# CAN-to-CAN.net
KiCad netlist of a schematic drawn in Altium Designer
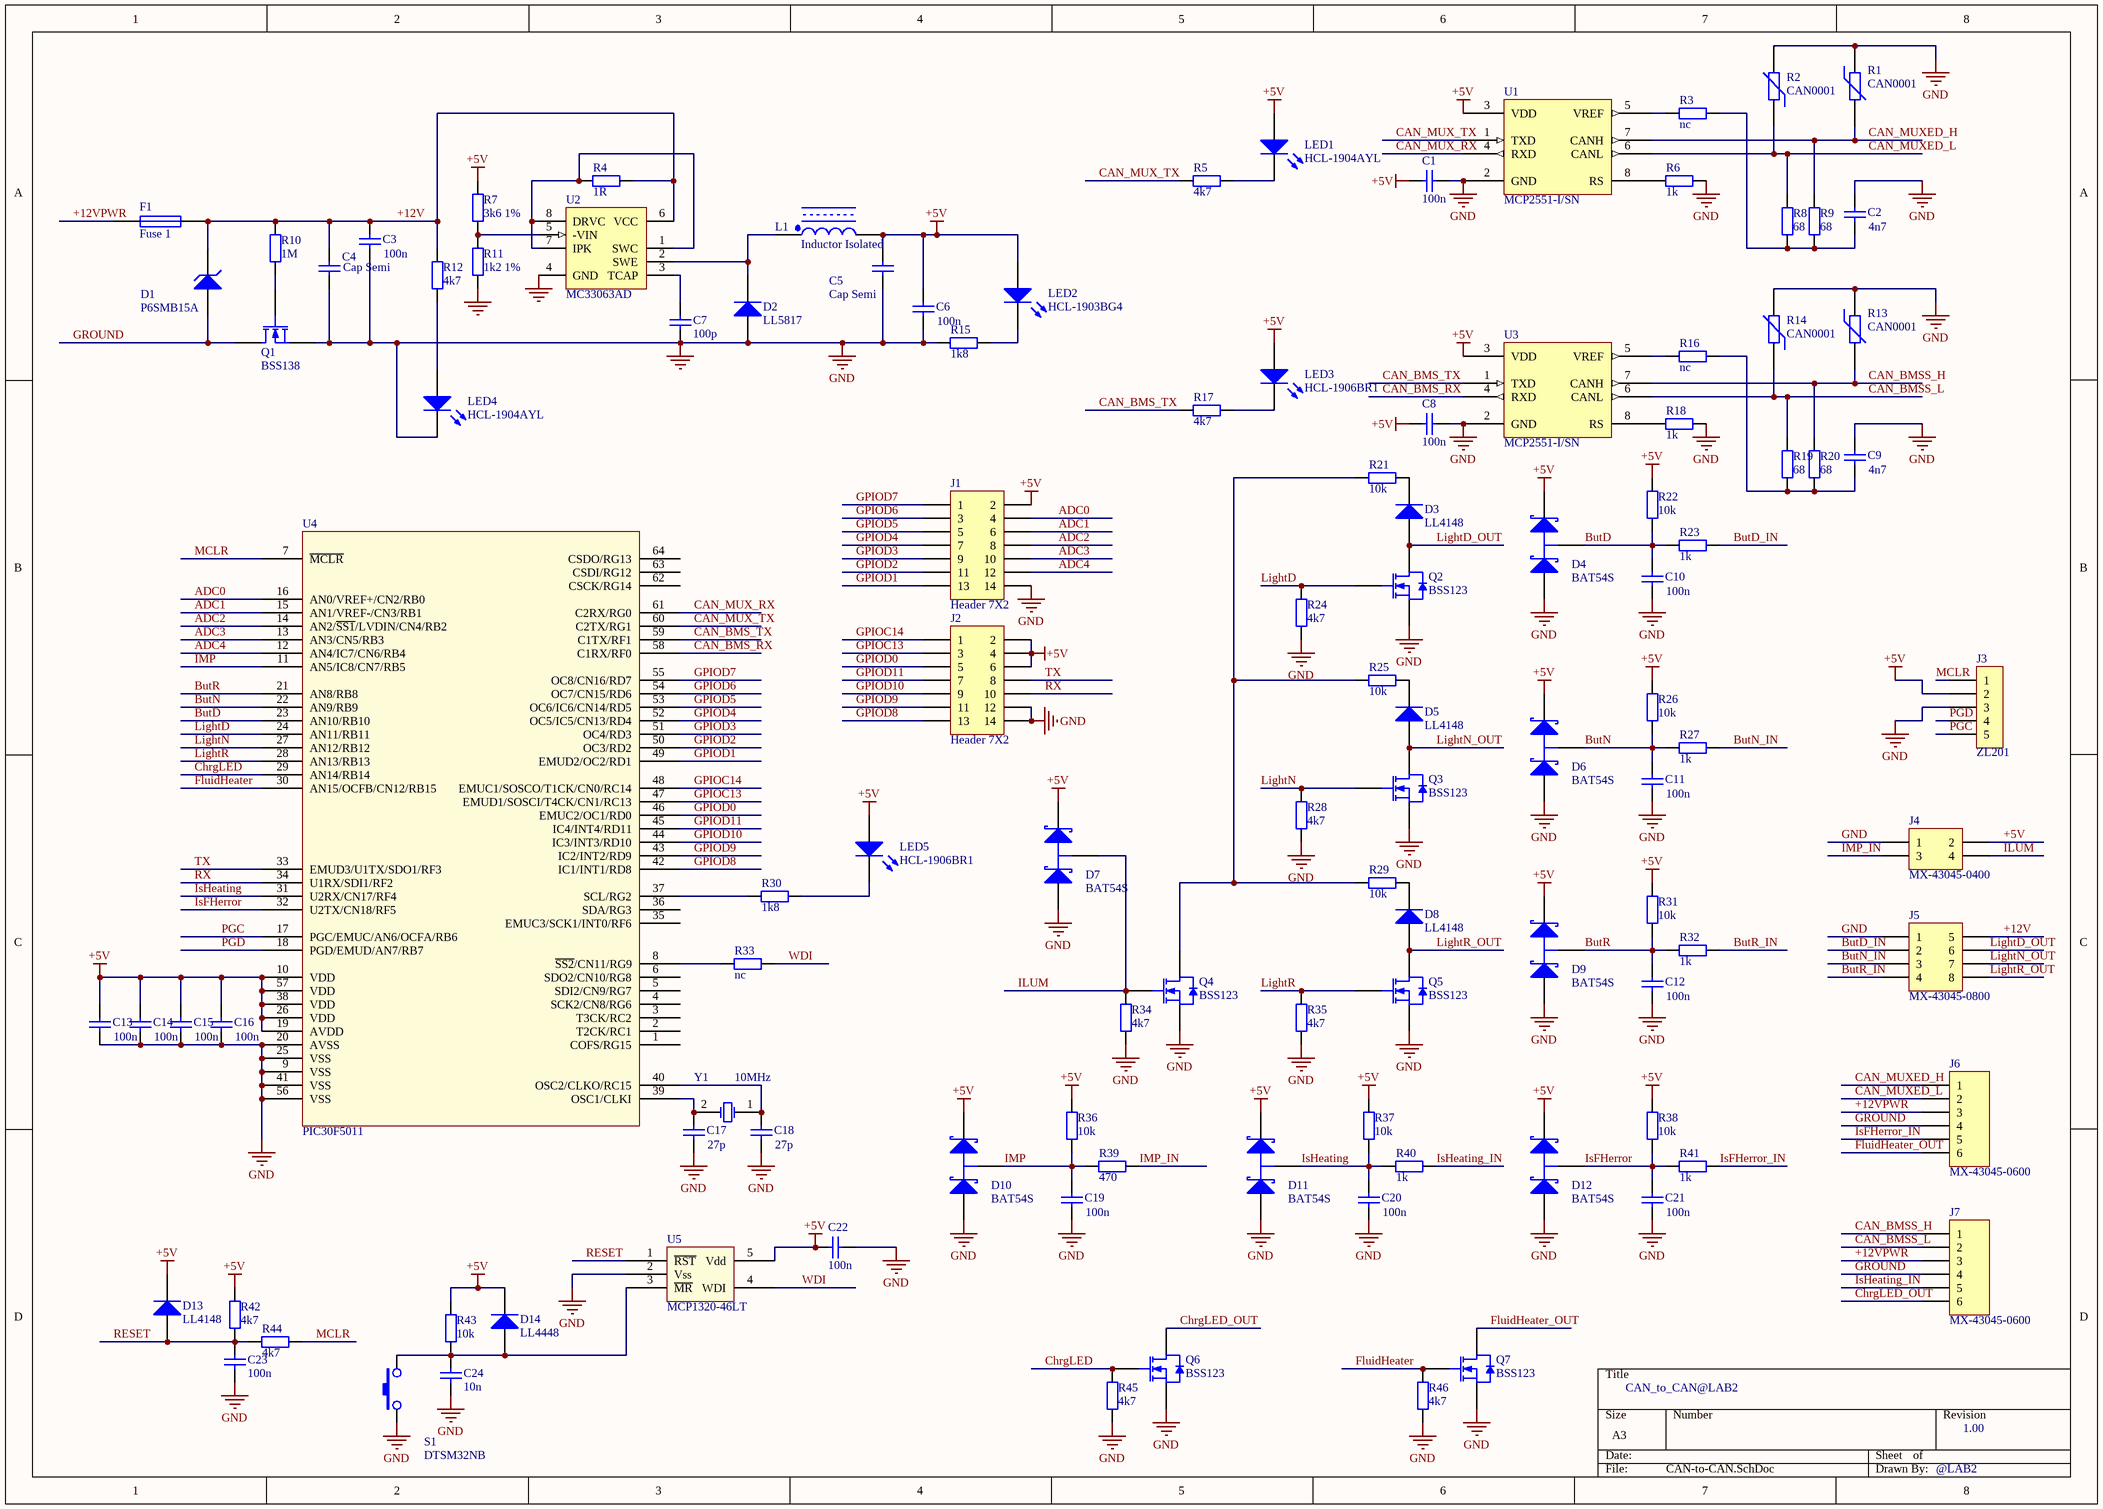
[diagram p0: CAN-to-CAN.SchDoc]

(export (version "E")
  (design (tool "Eeschema 10.0.6"))
  (components
    (comp (ref "C1")
      (value "100n")
      (footprint "0603")
      (description "Capacitor")
      (libsource (lib "Miscellaneous Devices") (part "Cap"))
    )
    (comp (ref "C2")
      (value "4n7")
      (footprint "0603")
      (description "Capacitor")
      (libsource (lib "Miscellaneous Devices") (part "Cap"))
    )
    (comp (ref "C3")
      (value "100n")
      (footprint "6-0805_N")
      (description "Capacitor")
      (libsource (lib "Miscellaneous Devices") (part "Cap"))
    )
    (comp (ref "C4")
      (value "Cap Semi")
      (footprint "C1206")
      (description "Capacitor (Semiconductor SIM Model)")
      (libsource (lib "Miscellaneous Devices") (part "Cap Semi"))
    )
    (comp (ref "C5")
      (value "Cap Semi")
      (footprint "C1206")
      (description "Capacitor (Semiconductor SIM Model)")
      (libsource (lib "Miscellaneous Devices") (part "Cap Semi"))
    )
    (comp (ref "C6")
      (value "100n")
      (footprint "0603")
      (description "Capacitor")
      (libsource (lib "Miscellaneous Devices") (part "Cap"))
    )
    (comp (ref "C7")
      (value "100p")
      (footprint "0603")
      (description "Capacitor")
      (libsource (lib "Miscellaneous Devices") (part "Cap"))
    )
    (comp (ref "C8")
      (value "100n")
      (footprint "0603")
      (description "Capacitor")
      (libsource (lib "Miscellaneous Devices") (part "Cap"))
    )
    (comp (ref "C9")
      (value "4n7")
      (footprint "0603")
      (description "Capacitor")
      (libsource (lib "Miscellaneous Devices") (part "Cap"))
    )
    (comp (ref "C10")
      (value "100n")
      (footprint "0603")
      (description "Capacitor")
      (libsource (lib "Miscellaneous Devices") (part "Cap"))
    )
    (comp (ref "C11")
      (value "100n")
      (footprint "0603")
      (description "Capacitor")
      (libsource (lib "Miscellaneous Devices") (part "Cap"))
    )
    (comp (ref "C12")
      (value "100n")
      (footprint "0603")
      (description "Capacitor")
      (libsource (lib "Miscellaneous Devices") (part "Cap"))
    )
    (comp (ref "C13")
      (value "100n")
      (footprint "0603")
      (description "Capacitor")
      (libsource (lib "Miscellaneous Devices") (part "Cap"))
    )
    (comp (ref "C14")
      (value "100n")
      (footprint "0603")
      (description "Capacitor")
      (libsource (lib "Miscellaneous Devices") (part "Cap"))
    )
    (comp (ref "C15")
      (value "100n")
      (footprint "0603")
      (description "Capacitor")
      (libsource (lib "Miscellaneous Devices") (part "Cap"))
    )
    (comp (ref "C16")
      (value "100n")
      (footprint "0603")
      (description "Capacitor")
      (libsource (lib "Miscellaneous Devices") (part "Cap"))
    )
    (comp (ref "C17")
      (value "27p")
      (footprint "0603")
      (description "Capacitor")
      (libsource (lib "Miscellaneous Devices") (part "Cap"))
    )
    (comp (ref "C18")
      (value "27p")
      (footprint "0603")
      (description "Capacitor")
      (libsource (lib "Miscellaneous Devices") (part "Cap"))
    )
    (comp (ref "C19")
      (value "100n")
      (footprint "0603")
      (description "Capacitor")
      (libsource (lib "Miscellaneous Devices") (part "Cap"))
    )
    (comp (ref "C20")
      (value "100n")
      (footprint "0603")
      (description "Capacitor")
      (libsource (lib "Miscellaneous Devices") (part "Cap"))
    )
    (comp (ref "C21")
      (value "100n")
      (footprint "0603")
      (description "Capacitor")
      (libsource (lib "Miscellaneous Devices") (part "Cap"))
    )
    (comp (ref "C22")
      (value "100n")
      (footprint "0603")
      (description "Capacitor")
      (libsource (lib "Miscellaneous Devices") (part "Cap"))
    )
    (comp (ref "C23")
      (value "100n")
      (footprint "0603")
      (description "Capacitor")
      (libsource (lib "Miscellaneous Devices") (part "Cap"))
    )
    (comp (ref "C24")
      (value "10n")
      (footprint "0603")
      (description "Capacitor")
      (libsource (lib "Miscellaneous Devices") (part "Cap"))
    )
    (comp (ref "D1")
      (value "P6SMB15A")
      (footprint "SMB")
      (description "Zener Diode")
      (libsource (lib "Miscellaneous Devices") (part "D Zener"))
    )
    (comp (ref "D2")
      (value "LL5817")
      (footprint "DIODE_SMC")
      (description "High Conductance Fast Diode")
      (libsource (lib "FSC Discrete Diode") (part "1N4148"))
    )
    (comp (ref "D3")
      (value "LL4148")
      (footprint "DIODE_SMC")
      (description "High Conductance Fast Diode")
      (libsource (lib "FSC Discrete Diode") (part "1N4148"))
    )
    (comp (ref "D4")
      (value "BAT54S")
      (footprint "SOT23_M")
      (description "Schottky Barrier Double Diode")
      (libsource (lib "Philips Discrete Diode - Schottky") (part "BAT54S"))
    )
    (comp (ref "D5")
      (value "LL4148")
      (footprint "DIODE_SMC")
      (description "High Conductance Fast Diode")
      (libsource (lib "FSC Discrete Diode") (part "1N4148"))
    )
    (comp (ref "D6")
      (value "BAT54S")
      (footprint "SOT23_M")
      (description "Schottky Barrier Double Diode")
      (libsource (lib "Philips Discrete Diode - Schottky") (part "BAT54S"))
    )
    (comp (ref "D7")
      (value "BAT54S")
      (footprint "SOT23_M")
      (description "Schottky Barrier Double Diode")
      (libsource (lib "Philips Discrete Diode - Schottky") (part "BAT54S"))
    )
    (comp (ref "D8")
      (value "LL4148")
      (footprint "DIODE_SMC")
      (description "High Conductance Fast Diode")
      (libsource (lib "FSC Discrete Diode") (part "1N4148"))
    )
    (comp (ref "D9")
      (value "BAT54S")
      (footprint "SOT23_M")
      (description "Schottky Barrier Double Diode")
      (libsource (lib "Philips Discrete Diode - Schottky") (part "BAT54S"))
    )
    (comp (ref "D10")
      (value "BAT54S")
      (footprint "SOT23_M")
      (description "Schottky Barrier Double Diode")
      (libsource (lib "Philips Discrete Diode - Schottky") (part "BAT54S"))
    )
    (comp (ref "D11")
      (value "BAT54S")
      (footprint "SOT23_M")
      (description "Schottky Barrier Double Diode")
      (libsource (lib "Philips Discrete Diode - Schottky") (part "BAT54S"))
    )
    (comp (ref "D12")
      (value "BAT54S")
      (footprint "SOT23_M")
      (description "Schottky Barrier Double Diode")
      (libsource (lib "Philips Discrete Diode - Schottky") (part "BAT54S"))
    )
    (comp (ref "D13")
      (value "LL4148")
      (footprint "DIODE_SMC")
      (description "High Conductance Fast Diode")
      (libsource (lib "FSC Discrete Diode") (part "1N4148"))
    )
    (comp (ref "D14")
      (value "LL4448")
      (footprint "DIODE_SMC")
      (description "Default Diode")
      (libsource (lib "Miscellaneous Devices") (part "Diode"))
    )
    (comp (ref "F1")
      (value "Fuse 1")
      (footprint "1812")
      (description "Fuse")
      (libsource (lib "Miscellaneous Devices") (part "Fuse 1"))
    )
    (comp (ref "J1")
      (value "Header 7X2")
      (footprint "HDR2X7")
      (description "Header, 7-Pin, Dual row")
      (libsource (lib "Miscellaneous Connectors") (part "Header 7X2"))
    )
    (comp (ref "J2")
      (value "Header 7X2")
      (footprint "HDR2X7")
      (description "Header, 7-Pin, Dual row")
      (libsource (lib "Miscellaneous Connectors") (part "Header 7X2"))
    )
    (comp (ref "J3")
      (value "ZL201")
      (footprint "HDR1X5")
      (description "Connector")
      (libsource (lib "*") (part "CON5"))
    )
    (comp (ref "J4")
      (value "MX-43045-0400")
      (footprint "HDR2X2")
      (description "Header, 2-Pin, Dual row")
      (libsource (lib "Miscellaneous Connectors") (part "Header 2X2"))
    )
    (comp (ref "J5")
      (value "MX-43045-0800")
      (footprint "HDR2X4")
      (description "Header, 4-Pin, Dual row")
      (libsource (lib "Miscellaneous Connectors") (part "Header 4X2A"))
    )
    (comp (ref "J6")
      (value "MX-43045-0600")
      (footprint "Miscellaneous Connectors:HDR2X3")
      (description "Header, 6-Pin")
      (libsource (lib "Miscellaneous Connectors") (part "Header 6"))
    )
    (comp (ref "J7")
      (value "MX-43045-0600")
      (footprint "HDR2X3")
      (description "Header, 6-Pin")
      (libsource (lib "Miscellaneous Connectors") (part "Header 6"))
    )
    (comp (ref "L1")
      (value "Inductor Isolated")
      (footprint "425")
      (description "Isolated Inductor")
      (libsource (lib "Miscellaneous Devices") (part "Inductor Isolated"))
    )
    (comp (ref "LED1")
      (value "HCL-1904AYL")
      (footprint "0603")
      (description "Typical BLUE SiC LED")
      (libsource (lib "Miscellaneous Devices") (part "LED3"))
    )
    (comp (ref "LED2")
      (value "HCL-1903BG4")
      (footprint "0603")
      (description "Typical BLUE SiC LED")
      (libsource (lib "Miscellaneous Devices") (part "LED3"))
    )
    (comp (ref "LED3")
      (value "HCL-1906BR1")
      (footprint "0603")
      (description "Typical BLUE SiC LED")
      (libsource (lib "Miscellaneous Devices") (part "LED3"))
    )
    (comp (ref "LED4")
      (value "HCL-1904AYL")
      (footprint "0603")
      (description "Typical BLUE SiC LED")
      (libsource (lib "Miscellaneous Devices") (part "LED3"))
    )
    (comp (ref "LED5")
      (value "HCL-1906BR1")
      (footprint "0603")
      (description "Typical BLUE SiC LED")
      (libsource (lib "Miscellaneous Devices") (part "LED3"))
    )
    (comp (ref "Q1")
      (value "BSS138")
      (footprint "SOT-23_M")
      (description "N-Channel Enhancement Mode Vertical DMOS FET")
      (libsource (lib "Zetex Discrete MOSFET") (part "BSS138"))
    )
    (comp (ref "Q2")
      (value "BSS123")
      (footprint "SOT23_M")
      (description "N-channel Enhancement Mode Vertical D-MOSFET")
      (libsource (lib "Philips Discrete MOSFET - Low Power") (part "BSS123"))
    )
    (comp (ref "Q3")
      (value "BSS123")
      (footprint "SOT23_M")
      (description "N-channel Enhancement Mode Vertical D-MOSFET")
      (libsource (lib "Philips Discrete MOSFET - Low Power") (part "BSS123"))
    )
    (comp (ref "Q4")
      (value "BSS123")
      (footprint "SOT23_M")
      (description "N-channel Enhancement Mode Vertical D-MOSFET")
      (libsource (lib "Philips Discrete MOSFET - Low Power") (part "BSS123"))
    )
    (comp (ref "Q5")
      (value "BSS123")
      (footprint "SOT23_M")
      (description "N-channel Enhancement Mode Vertical D-MOSFET")
      (libsource (lib "Philips Discrete MOSFET - Low Power") (part "BSS123"))
    )
    (comp (ref "Q6")
      (value "BSS123")
      (footprint "SOT23_N")
      (description "N-channel Enhancement Mode Vertical D-MOSFET")
      (libsource (lib "Philips Discrete MOSFET - Low Power") (part "BSS123"))
    )
    (comp (ref "Q7")
      (value "BSS123")
      (footprint "SOT23_M")
      (description "N-channel Enhancement Mode Vertical D-MOSFET")
      (libsource (lib "Philips Discrete MOSFET - Low Power") (part "BSS123"))
    )
    (comp (ref "R1")
      (value "CAN0001")
      (footprint "0603")
      (description "Varistor (Voltage-Sensitive Resistor)")
      (libsource (lib "Miscellaneous Devices") (part "Res Varistor"))
    )
    (comp (ref "R2")
      (value "CAN0001")
      (footprint "0603")
      (description "Varistor (Voltage-Sensitive Resistor)")
      (libsource (lib "Miscellaneous Devices") (part "Res Varistor"))
    )
    (comp (ref "R3")
      (value "nc")
      (footprint "0603")
      (description "Resistor")
      (libsource (lib "") (part "Res2_2"))
    )
    (comp (ref "R4")
      (value "1R")
      (footprint "AXIAL-0.4")
      (description "Resistor")
      (libsource (lib "") (part "Res2_2"))
    )
    (comp (ref "R5")
      (value "4k7")
      (footprint "0603")
      (description "Resistor")
      (libsource (lib "Miscellaneous Devices") (part "Res2"))
    )
    (comp (ref "R6")
      (value "1k")
      (footprint "0603")
      (description "Resistor")
      (libsource (lib "") (part "Res2_2"))
    )
    (comp (ref "R7")
      (value "3k6 1%")
      (footprint "0603")
      (description "Resistor")
      (libsource (lib "") (part "Res2_1"))
    )
    (comp (ref "R8")
      (value "68")
      (footprint "0603")
      (description "Resistor")
      (libsource (lib "") (part "Res2_1"))
    )
    (comp (ref "R9")
      (value "68")
      (footprint "0603")
      (description "Resistor")
      (libsource (lib "") (part "Res2_1"))
    )
    (comp (ref "R10")
      (value "1M")
      (footprint "0603")
      (description "Resistor")
      (libsource (lib "") (part "Res2_1"))
    )
    (comp (ref "R11")
      (value "1k2 1%")
      (footprint "0603")
      (description "Resistor")
      (libsource (lib "") (part "Res2_3"))
    )
    (comp (ref "R12")
      (value "4k7")
      (footprint "0603")
      (description "Resistor")
      (libsource (lib "") (part "Res2_1"))
    )
    (comp (ref "R13")
      (value "CAN0001")
      (footprint "0603")
      (description "Varistor (Voltage-Sensitive Resistor)")
      (libsource (lib "Miscellaneous Devices") (part "Res Varistor"))
    )
    (comp (ref "R14")
      (value "CAN0001")
      (footprint "0603")
      (description "Varistor (Voltage-Sensitive Resistor)")
      (libsource (lib "Miscellaneous Devices") (part "Res Varistor"))
    )
    (comp (ref "R15")
      (value "1k8")
      (footprint "0603")
      (description "Resistor")
      (libsource (lib "Miscellaneous Devices") (part "Res2"))
    )
    (comp (ref "R16")
      (value "nc")
      (footprint "0603")
      (description "Resistor")
      (libsource (lib "") (part "Res2_2"))
    )
    (comp (ref "R17")
      (value "4k7")
      (footprint "0603")
      (description "Resistor")
      (libsource (lib "Miscellaneous Devices") (part "Res2"))
    )
    (comp (ref "R18")
      (value "1k")
      (footprint "0603")
      (description "Resistor")
      (libsource (lib "") (part "Res2_2"))
    )
    (comp (ref "R19")
      (value "68")
      (footprint "0603")
      (description "Resistor")
      (libsource (lib "") (part "Res2_1"))
    )
    (comp (ref "R20")
      (value "68")
      (footprint "0603")
      (description "Resistor")
      (libsource (lib "") (part "Res2_1"))
    )
    (comp (ref "R21")
      (value "10k")
      (footprint "0603")
      (description "Resistor")
      (libsource (lib "") (part "Res2_2"))
    )
    (comp (ref "R22")
      (value "10k")
      (footprint "0603")
      (description "Resistor")
      (libsource (lib "") (part "Res2_1"))
    )
    (comp (ref "R23")
      (value "1k")
      (footprint "0603")
      (description "Resistor")
      (libsource (lib "Miscellaneous Devices") (part "Res2"))
    )
    (comp (ref "R24")
      (value "4k7")
      (footprint "0603")
      (description "Resistor")
      (libsource (lib "") (part "Res2_1"))
    )
    (comp (ref "R25")
      (value "10k")
      (footprint "0603")
      (description "Resistor")
      (libsource (lib "") (part "Res2_2"))
    )
    (comp (ref "R26")
      (value "10k")
      (footprint "0603")
      (description "Resistor")
      (libsource (lib "") (part "Res2_1"))
    )
    (comp (ref "R27")
      (value "1k")
      (footprint "0603")
      (description "Resistor")
      (libsource (lib "Miscellaneous Devices") (part "Res2"))
    )
    (comp (ref "R28")
      (value "4k7")
      (footprint "0603")
      (description "Resistor")
      (libsource (lib "") (part "Res2_1"))
    )
    (comp (ref "R29")
      (value "10k")
      (footprint "0603")
      (description "Resistor")
      (libsource (lib "") (part "Res2_2"))
    )
    (comp (ref "R30")
      (value "1k8")
      (footprint "0603")
      (description "Resistor")
      (libsource (lib "Miscellaneous Devices") (part "Res2"))
    )
    (comp (ref "R31")
      (value "10k")
      (footprint "0603")
      (description "Resistor")
      (libsource (lib "") (part "Res2_1"))
    )
    (comp (ref "R32")
      (value "1k")
      (footprint "0603")
      (description "Resistor")
      (libsource (lib "Miscellaneous Devices") (part "Res2"))
    )
    (comp (ref "R33")
      (value "nc")
      (footprint "0603")
      (description "Resistor")
      (libsource (lib "Miscellaneous Devices") (part "Res2"))
    )
    (comp (ref "R34")
      (value "4k7")
      (footprint "0603")
      (description "Resistor")
      (libsource (lib "") (part "Res2_1"))
    )
    (comp (ref "R35")
      (value "4k7")
      (footprint "0603")
      (description "Resistor")
      (libsource (lib "") (part "Res2_1"))
    )
    (comp (ref "R36")
      (value "10k")
      (footprint "0603")
      (description "Resistor")
      (libsource (lib "") (part "Res2_1"))
    )
    (comp (ref "R37")
      (value "10k")
      (footprint "0603")
      (description "Resistor")
      (libsource (lib "") (part "Res2_1"))
    )
    (comp (ref "R38")
      (value "10k")
      (footprint "0603")
      (description "Resistor")
      (libsource (lib "") (part "Res2_1"))
    )
    (comp (ref "R39")
      (value "470")
      (footprint "0603")
      (description "Resistor")
      (libsource (lib "Miscellaneous Devices") (part "Res2"))
    )
    (comp (ref "R40")
      (value "1k")
      (footprint "0603")
      (description "Resistor")
      (libsource (lib "Miscellaneous Devices") (part "Res2"))
    )
    (comp (ref "R41")
      (value "1k")
      (footprint "0603")
      (description "Resistor")
      (libsource (lib "Miscellaneous Devices") (part "Res2"))
    )
    (comp (ref "R42")
      (value "4k7")
      (footprint "0603")
      (description "Resistor")
      (libsource (lib "") (part "Res2_1"))
    )
    (comp (ref "R43")
      (value "10k")
      (footprint "0603")
      (description "Resistor")
      (libsource (lib "") (part "Res2_3"))
    )
    (comp (ref "R44")
      (value "4k7")
      (footprint "0603")
      (description "Resistor")
      (libsource (lib "Miscellaneous Devices") (part "Res2"))
    )
    (comp (ref "R45")
      (value "4k7")
      (footprint "0603")
      (description "Resistor")
      (libsource (lib "") (part "Res2_1"))
    )
    (comp (ref "R46")
      (value "4k7")
      (footprint "0603")
      (description "Resistor")
      (libsource (lib "") (part "Res2_1"))
    )
    (comp (ref "S1")
      (value "DTSM32NB")
      (footprint "0603")
      (description "Switch PushButton")
      (libsource (lib "*") (part "PUSHB"))
    )
    (comp (ref "U1")
      (value "MCP2551-I/SN")
      (footprint "SO8_L")
      (description "High Speed CAN Transceiver, 8-Pin Plastic SOIC, Industrial Grade")
      (libsource (lib "Microchip Interface Line Transceiver") (part "MCP2551-I/SN"))
    )
    (comp (ref "U2")
      (value "MC33063AD")
      (footprint "SO8_N")
      (description "DC-to-DC Converter Control Circuit")
      (libsource (lib "Motorola Power Mgt DC-DC Converter") (part "MC33063AD"))
    )
    (comp (ref "U3")
      (value "MCP2551-I/SN")
      (footprint "SO8_L")
      (description "High Speed CAN Transceiver, 8-Pin Plastic SOIC, Industrial Grade")
      (libsource (lib "Microchip Interface Line Transceiver") (part "MCP2551-I/SN"))
    )
    (comp (ref "U4")
      (value "PIC30F5011")
      (footprint "ST-64-2_M")
      (description "PIC30F5011 - Up")
      (libsource (lib "X-Tro's Misc") (part "PIC30F5011"))
    )
    (comp (ref "U5")
      (value "MCP1320-46LT")
      (footprint "SOT23-6_L")
      (libsource (lib "X-Tro's Misc") (part "MCP1320"))
    )
    (comp (ref "Y1")
      (value "10MHz")
      (footprint "3.2X1.6X1.1")
      (description "Crystal Oscillator")
      (libsource (lib "Miscellaneous Devices") (part "XTAL"))
    )
  )
  (nets
    (net (code "1") (name "+5V") (class "Default")
      (node (ref "C1") (pin "1") (pinfunction "1_1") (pintype "passive"))
      (node (ref "C13") (pin "1") (pinfunction "1_1") (pintype "passive"))
      (node (ref "C14") (pin "1") (pinfunction "1_1") (pintype "passive"))
      (node (ref "C15") (pin "1") (pinfunction "1_1") (pintype "passive"))
      (node (ref "C16") (pin "1") (pinfunction "1_1") (pintype "passive"))
      (node (ref "C22") (pin "1") (pinfunction "1_1") (pintype "passive"))
      (node (ref "C5") (pin "1") (pinfunction "1_1") (pintype "passive"))
      (node (ref "C6") (pin "1") (pinfunction "1_1") (pintype "passive"))
      (node (ref "C8") (pin "1") (pinfunction "1_1") (pintype "passive"))
      (node (ref "D10") (pin "2") (pinfunction "K_2") (pintype "passive"))
      (node (ref "D11") (pin "2") (pinfunction "K_2") (pintype "passive"))
      (node (ref "D12") (pin "2") (pinfunction "K_2") (pintype "passive"))
      (node (ref "D13") (pin "2") (pinfunction "K_2") (pintype "passive"))
      (node (ref "D14") (pin "2") (pinfunction "K_2") (pintype "passive"))
      (node (ref "D4") (pin "2") (pinfunction "K_2") (pintype "passive"))
      (node (ref "D6") (pin "2") (pinfunction "K_2") (pintype "passive"))
      (node (ref "D7") (pin "2") (pinfunction "K_2") (pintype "passive"))
      (node (ref "D9") (pin "2") (pinfunction "K_2") (pintype "passive"))
      (node (ref "J1") (pin "2") (pinfunction "2_2") (pintype "passive"))
      (node (ref "J2") (pin "2") (pinfunction "2_2") (pintype "passive"))
      (node (ref "J2") (pin "4") (pinfunction "4_4") (pintype "passive"))
      (node (ref "J2") (pin "6") (pinfunction "6_6") (pintype "passive"))
      (node (ref "J3") (pin "2") (pinfunction "2_2") (pintype "passive"))
      (node (ref "J4") (pin "2") (pinfunction "2_2") (pintype "passive"))
      (node (ref "L1") (pin "2") (pinfunction "2_2") (pintype "passive"))
      (node (ref "LED1") (pin "1") (pinfunction "A_1") (pintype "passive"))
      (node (ref "LED2") (pin "1") (pinfunction "A_1") (pintype "passive"))
      (node (ref "LED3") (pin "1") (pinfunction "A_1") (pintype "passive"))
      (node (ref "LED5") (pin "1") (pinfunction "A_1") (pintype "passive"))
      (node (ref "R22") (pin "1") (pinfunction "1_1") (pintype "passive"))
      (node (ref "R26") (pin "1") (pinfunction "1_1") (pintype "passive"))
      (node (ref "R31") (pin "1") (pinfunction "1_1") (pintype "passive"))
      (node (ref "R36") (pin "1") (pinfunction "1_1") (pintype "passive"))
      (node (ref "R37") (pin "1") (pinfunction "1_1") (pintype "passive"))
      (node (ref "R38") (pin "1") (pinfunction "1_1") (pintype "passive"))
      (node (ref "R42") (pin "1") (pinfunction "1_1") (pintype "passive"))
      (node (ref "R43") (pin "2") (pinfunction "2_2") (pintype "passive"))
      (node (ref "R7") (pin "1") (pinfunction "1_1") (pintype "passive"))
      (node (ref "U1") (pin "3") (pinfunction "VDD_3") (pintype "power_in"))
      (node (ref "U3") (pin "3") (pinfunction "VDD_3") (pintype "power_in"))
      (node (ref "U4") (pin "10") (pinfunction "VDD_10") (pintype "passive"))
      (node (ref "U4") (pin "19") (pinfunction "AVDD_19") (pintype "passive"))
      (node (ref "U4") (pin "26") (pinfunction "VDD_26") (pintype "passive"))
      (node (ref "U4") (pin "38") (pinfunction "VDD_38") (pintype "passive"))
      (node (ref "U4") (pin "57") (pinfunction "VDD_57") (pintype "passive"))
      (node (ref "U5") (pin "5") (pinfunction "Vdd_5") (pintype "passive"))
    )
    (net (code "2") (name "/+12V") (class "Default")
      (node (ref "C3") (pin "1") (pinfunction "1_1") (pintype "passive"))
      (node (ref "C4") (pin "1") (pinfunction "1_1") (pintype "passive"))
      (node (ref "D1") (pin "2") (pinfunction "K_2") (pintype "passive"))
      (node (ref "F1") (pin "2") (pinfunction "2_2") (pintype "passive"))
      (node (ref "J5") (pin "5") (pinfunction "5_5") (pintype "passive"))
      (node (ref "R10") (pin "1") (pinfunction "1_1") (pintype "passive"))
      (node (ref "R12") (pin "1") (pinfunction "1_1") (pintype "passive"))
      (node (ref "R4") (pin "2") (pinfunction "2_2") (pintype "passive"))
      (node (ref "U2") (pin "6") (pinfunction "VCC_6") (pintype "power_in"))
    )
    (net (code "3") (name "/+12VPWR") (class "Default")
      (node (ref "F1") (pin "1") (pinfunction "1_1") (pintype "passive"))
      (node (ref "J6") (pin "3") (pinfunction "3_3") (pintype "passive"))
      (node (ref "J7") (pin "3") (pinfunction "3_3") (pintype "passive"))
    )
    (net (code "4") (name "/ADC0") (class "Default")
      (node (ref "J1") (pin "4") (pinfunction "4_4") (pintype "passive"))
      (node (ref "U4") (pin "16") (pinfunction "AN0/VREF+/CN2/RB0_16") (pintype "passive"))
    )
    (net (code "5") (name "/ADC1") (class "Default")
      (node (ref "J1") (pin "6") (pinfunction "6_6") (pintype "passive"))
      (node (ref "U4") (pin "15") (pinfunction "AN1/VREF-/CN3/RB1_15") (pintype "passive"))
    )
    (net (code "6") (name "/ADC2") (class "Default")
      (node (ref "J1") (pin "8") (pinfunction "8_8") (pintype "passive"))
      (node (ref "U4") (pin "14") (pinfunction "AN2/~{SS1}/LVDIN/CN4/RB2_14") (pintype "passive"))
    )
    (net (code "7") (name "/ADC3") (class "Default")
      (node (ref "J1") (pin "10") (pinfunction "10_10") (pintype "passive"))
      (node (ref "U4") (pin "13") (pinfunction "AN3/CN5/RB3_13") (pintype "passive"))
    )
    (net (code "8") (name "/ADC4") (class "Default")
      (node (ref "J1") (pin "12") (pinfunction "12_12") (pintype "passive"))
      (node (ref "U4") (pin "12") (pinfunction "AN4/IC7/CN6/RB4_12") (pintype "passive"))
    )
    (net (code "9") (name "/ButD") (class "Default")
      (node (ref "C10") (pin "1") (pinfunction "1_1") (pintype "passive"))
      (node (ref "D4") (pin "3") (pinfunction "C_3") (pintype "passive"))
      (node (ref "R22") (pin "2") (pinfunction "2_2") (pintype "passive"))
      (node (ref "R23") (pin "2") (pinfunction "2_2") (pintype "passive"))
      (node (ref "U4") (pin "23") (pinfunction "AN10/RB10_23") (pintype "passive"))
    )
    (net (code "10") (name "/ButD_IN") (class "Default")
      (node (ref "J5") (pin "2") (pinfunction "2_2") (pintype "passive"))
      (node (ref "R23") (pin "1") (pinfunction "1_1") (pintype "passive"))
    )
    (net (code "11") (name "/ButN") (class "Default")
      (node (ref "C11") (pin "1") (pinfunction "1_1") (pintype "passive"))
      (node (ref "D6") (pin "3") (pinfunction "C_3") (pintype "passive"))
      (node (ref "R26") (pin "2") (pinfunction "2_2") (pintype "passive"))
      (node (ref "R27") (pin "2") (pinfunction "2_2") (pintype "passive"))
      (node (ref "U4") (pin "22") (pinfunction "AN9/RB9_22") (pintype "passive"))
    )
    (net (code "12") (name "/ButN_IN") (class "Default")
      (node (ref "J5") (pin "3") (pinfunction "3_3") (pintype "passive"))
      (node (ref "R27") (pin "1") (pinfunction "1_1") (pintype "passive"))
    )
    (net (code "13") (name "/ButR") (class "Default")
      (node (ref "C12") (pin "1") (pinfunction "1_1") (pintype "passive"))
      (node (ref "D9") (pin "3") (pinfunction "C_3") (pintype "passive"))
      (node (ref "R31") (pin "2") (pinfunction "2_2") (pintype "passive"))
      (node (ref "R32") (pin "2") (pinfunction "2_2") (pintype "passive"))
      (node (ref "U4") (pin "21") (pinfunction "AN8/RB8_21") (pintype "passive"))
    )
    (net (code "14") (name "/ButR_IN") (class "Default")
      (node (ref "J5") (pin "4") (pinfunction "4_4") (pintype "passive"))
      (node (ref "R32") (pin "1") (pinfunction "1_1") (pintype "passive"))
    )
    (net (code "15") (name "/CAN_BMSS_H") (class "Default")
      (node (ref "J7") (pin "1") (pinfunction "1_1") (pintype "passive"))
      (node (ref "R13") (pin "2") (pinfunction "2_2") (pintype "passive"))
      (node (ref "R20") (pin "1") (pinfunction "1_1") (pintype "passive"))
      (node (ref "U3") (pin "7") (pinfunction "CANH_7") (pintype "output"))
    )
    (net (code "16") (name "/CAN_BMSS_L") (class "Default")
      (node (ref "J7") (pin "2") (pinfunction "2_2") (pintype "passive"))
      (node (ref "R14") (pin "1") (pinfunction "1_1") (pintype "passive"))
      (node (ref "R19") (pin "1") (pinfunction "1_1") (pintype "passive"))
      (node (ref "U3") (pin "6") (pinfunction "CANL_6") (pintype "output"))
    )
    (net (code "17") (name "/CAN_BMS_RX") (class "Default")
      (node (ref "U3") (pin "4") (pinfunction "RXD_4") (pintype "output"))
      (node (ref "U4") (pin "58") (pinfunction "C1RX/RF0_58") (pintype "passive"))
    )
    (net (code "18") (name "/CAN_BMS_TX") (class "Default")
      (node (ref "R17") (pin "2") (pinfunction "2_2") (pintype "passive"))
      (node (ref "U3") (pin "1") (pinfunction "TXD_1") (pintype "input"))
      (node (ref "U4") (pin "59") (pinfunction "C1TX/RF1_59") (pintype "passive"))
    )
    (net (code "19") (name "/CAN_MUXED_H") (class "Default")
      (node (ref "J6") (pin "1") (pinfunction "1_1") (pintype "passive"))
      (node (ref "R1") (pin "2") (pinfunction "2_2") (pintype "passive"))
      (node (ref "R9") (pin "1") (pinfunction "1_1") (pintype "passive"))
      (node (ref "U1") (pin "7") (pinfunction "CANH_7") (pintype "output"))
    )
    (net (code "20") (name "/CAN_MUXED_L") (class "Default")
      (node (ref "J6") (pin "2") (pinfunction "2_2") (pintype "passive"))
      (node (ref "R2") (pin "1") (pinfunction "1_1") (pintype "passive"))
      (node (ref "R8") (pin "1") (pinfunction "1_1") (pintype "passive"))
      (node (ref "U1") (pin "6") (pinfunction "CANL_6") (pintype "output"))
    )
    (net (code "21") (name "/CAN_MUX_RX") (class "Default")
      (node (ref "U1") (pin "4") (pinfunction "RXD_4") (pintype "output"))
      (node (ref "U4") (pin "61") (pinfunction "C2RX/RG0_61") (pintype "passive"))
    )
    (net (code "22") (name "/CAN_MUX_TX") (class "Default")
      (node (ref "R5") (pin "2") (pinfunction "2_2") (pintype "passive"))
      (node (ref "U1") (pin "1") (pinfunction "TXD_1") (pintype "input"))
      (node (ref "U4") (pin "60") (pinfunction "C2TX/RG1_60") (pintype "passive"))
    )
    (net (code "23") (name "/ChrgLED") (class "Default")
      (node (ref "Q6") (pin "3") (pinfunction "G_3") (pintype "passive"))
      (node (ref "R45") (pin "1") (pinfunction "1_1") (pintype "passive"))
      (node (ref "U4") (pin "29") (pinfunction "AN14/RB14_29") (pintype "passive"))
    )
    (net (code "24") (name "/ChrgLED_OUT") (class "Default")
      (node (ref "J7") (pin "6") (pinfunction "6_6") (pintype "passive"))
      (node (ref "Q6") (pin "1") (pinfunction "D_1") (pintype "passive"))
    )
    (net (code "25") (name "/FluidHeater") (class "Default")
      (node (ref "Q7") (pin "3") (pinfunction "G_3") (pintype "passive"))
      (node (ref "R46") (pin "1") (pinfunction "1_1") (pintype "passive"))
      (node (ref "U4") (pin "30") (pinfunction "AN15/OCFB/CN12/RB15_30") (pintype "passive"))
    )
    (net (code "26") (name "/FluidHeater_OUT") (class "Default")
      (node (ref "J6") (pin "6") (pinfunction "6_6") (pintype "passive"))
      (node (ref "Q7") (pin "1") (pinfunction "D_1") (pintype "passive"))
    )
    (net (code "27") (name "/GPIOC13") (class "Default")
      (node (ref "J2") (pin "3") (pinfunction "3_3") (pintype "passive"))
      (node (ref "U4") (pin "47") (pinfunction "EMUD1/SOSCI/T4CK/CN1/RC13_47") (pintype "passive"))
    )
    (net (code "28") (name "/GPIOC14") (class "Default")
      (node (ref "J2") (pin "1") (pinfunction "1_1") (pintype "passive"))
      (node (ref "U4") (pin "48") (pinfunction "EMUC1/SOSCO/T1CK/CN0/RC14_48") (pintype "passive"))
    )
    (net (code "29") (name "/GPIOD0") (class "Default")
      (node (ref "J2") (pin "5") (pinfunction "5_5") (pintype "passive"))
      (node (ref "U4") (pin "46") (pinfunction "EMUC2/OC1/RD0_46") (pintype "passive"))
    )
    (net (code "30") (name "/GPIOD1") (class "Default")
      (node (ref "J1") (pin "13") (pinfunction "13_13") (pintype "passive"))
      (node (ref "U4") (pin "49") (pinfunction "EMUD2/OC2/RD1_49") (pintype "passive"))
    )
    (net (code "31") (name "/GPIOD2") (class "Default")
      (node (ref "J1") (pin "11") (pinfunction "11_11") (pintype "passive"))
      (node (ref "U4") (pin "50") (pinfunction "OC3/RD2_50") (pintype "passive"))
    )
    (net (code "32") (name "/GPIOD3") (class "Default")
      (node (ref "J1") (pin "9") (pinfunction "9_9") (pintype "passive"))
      (node (ref "U4") (pin "51") (pinfunction "OC4/RD3_51") (pintype "passive"))
    )
    (net (code "33") (name "/GPIOD4") (class "Default")
      (node (ref "J1") (pin "7") (pinfunction "7_7") (pintype "passive"))
      (node (ref "U4") (pin "52") (pinfunction "OC5/IC5/CN13/RD4_52") (pintype "passive"))
    )
    (net (code "34") (name "/GPIOD5") (class "Default")
      (node (ref "J1") (pin "5") (pinfunction "5_5") (pintype "passive"))
      (node (ref "U4") (pin "53") (pinfunction "OC6/IC6/CN14/RD5_53") (pintype "passive"))
    )
    (net (code "35") (name "/GPIOD6") (class "Default")
      (node (ref "J1") (pin "3") (pinfunction "3_3") (pintype "passive"))
      (node (ref "U4") (pin "54") (pinfunction "OC7/CN15/RD6_54") (pintype "passive"))
    )
    (net (code "36") (name "/GPIOD7") (class "Default")
      (node (ref "J1") (pin "1") (pinfunction "1_1") (pintype "passive"))
      (node (ref "U4") (pin "55") (pinfunction "OC8/CN16/RD7_55") (pintype "passive"))
    )
    (net (code "37") (name "/GPIOD8") (class "Default")
      (node (ref "J2") (pin "13") (pinfunction "13_13") (pintype "passive"))
      (node (ref "U4") (pin "42") (pinfunction "IC1/INT1/RD8_42") (pintype "passive"))
    )
    (net (code "38") (name "/GPIOD9") (class "Default")
      (node (ref "J2") (pin "11") (pinfunction "11_11") (pintype "passive"))
      (node (ref "U4") (pin "43") (pinfunction "IC2/INT2/RD9_43") (pintype "passive"))
    )
    (net (code "39") (name "/GPIOD10") (class "Default")
      (node (ref "J2") (pin "9") (pinfunction "9_9") (pintype "passive"))
      (node (ref "U4") (pin "44") (pinfunction "IC3/INT3/RD10_44") (pintype "passive"))
    )
    (net (code "40") (name "/GPIOD11") (class "Default")
      (node (ref "J2") (pin "7") (pinfunction "7_7") (pintype "passive"))
      (node (ref "U4") (pin "45") (pinfunction "IC4/INT4/RD11_45") (pintype "passive"))
    )
    (net (code "41") (name "/GROUND") (class "Default")
      (node (ref "D1") (pin "1") (pinfunction "A_1") (pintype "passive"))
      (node (ref "J6") (pin "4") (pinfunction "4_4") (pintype "passive"))
      (node (ref "J7") (pin "4") (pinfunction "4_4") (pintype "passive"))
      (node (ref "Q1") (pin "1") (pinfunction "D_1") (pintype "passive"))
    )
    (net (code "42") (name "/ILUM") (class "Default")
      (node (ref "D7") (pin "3") (pinfunction "C_3") (pintype "passive"))
      (node (ref "J4") (pin "4") (pinfunction "4_4") (pintype "passive"))
      (node (ref "Q4") (pin "3") (pinfunction "G_3") (pintype "passive"))
      (node (ref "R34") (pin "1") (pinfunction "1_1") (pintype "passive"))
    )
    (net (code "43") (name "/IMP") (class "Default")
      (node (ref "C19") (pin "1") (pinfunction "1_1") (pintype "passive"))
      (node (ref "D10") (pin "3") (pinfunction "C_3") (pintype "passive"))
      (node (ref "R36") (pin "2") (pinfunction "2_2") (pintype "passive"))
      (node (ref "R39") (pin "2") (pinfunction "2_2") (pintype "passive"))
      (node (ref "U4") (pin "11") (pinfunction "AN5/IC8/CN7/RB5_11") (pintype "passive"))
    )
    (net (code "44") (name "/IMP_IN") (class "Default")
      (node (ref "J4") (pin "3") (pinfunction "3_3") (pintype "passive"))
      (node (ref "R39") (pin "1") (pinfunction "1_1") (pintype "passive"))
    )
    (net (code "45") (name "/IsFHerror") (class "Default")
      (node (ref "C21") (pin "1") (pinfunction "1_1") (pintype "passive"))
      (node (ref "D12") (pin "3") (pinfunction "C_3") (pintype "passive"))
      (node (ref "R38") (pin "2") (pinfunction "2_2") (pintype "passive"))
      (node (ref "R41") (pin "2") (pinfunction "2_2") (pintype "passive"))
      (node (ref "U4") (pin "32") (pinfunction "U2TX/CN18/RF5_32") (pintype "passive"))
    )
    (net (code "46") (name "/IsFHerror_IN") (class "Default")
      (node (ref "J6") (pin "5") (pinfunction "5_5") (pintype "passive"))
      (node (ref "R41") (pin "1") (pinfunction "1_1") (pintype "passive"))
    )
    (net (code "47") (name "/IsHeating") (class "Default")
      (node (ref "C20") (pin "1") (pinfunction "1_1") (pintype "passive"))
      (node (ref "D11") (pin "3") (pinfunction "C_3") (pintype "passive"))
      (node (ref "R37") (pin "2") (pinfunction "2_2") (pintype "passive"))
      (node (ref "R40") (pin "2") (pinfunction "2_2") (pintype "passive"))
      (node (ref "U4") (pin "31") (pinfunction "U2RX/CN17/RF4_31") (pintype "passive"))
    )
    (net (code "48") (name "/IsHeating_IN") (class "Default")
      (node (ref "J7") (pin "5") (pinfunction "5_5") (pintype "passive"))
      (node (ref "R40") (pin "1") (pinfunction "1_1") (pintype "passive"))
    )
    (net (code "49") (name "/LightD") (class "Default")
      (node (ref "Q2") (pin "3") (pinfunction "G_3") (pintype "passive"))
      (node (ref "R24") (pin "1") (pinfunction "1_1") (pintype "passive"))
      (node (ref "U4") (pin "24") (pinfunction "AN11/RB11_24") (pintype "passive"))
    )
    (net (code "50") (name "/LightD_OUT") (class "Default")
      (node (ref "D3") (pin "1") (pinfunction "A_1") (pintype "passive"))
      (node (ref "J5") (pin "6") (pinfunction "6_6") (pintype "passive"))
      (node (ref "Q2") (pin "1") (pinfunction "D_1") (pintype "passive"))
    )
    (net (code "51") (name "/LightN") (class "Default")
      (node (ref "Q3") (pin "3") (pinfunction "G_3") (pintype "passive"))
      (node (ref "R28") (pin "1") (pinfunction "1_1") (pintype "passive"))
      (node (ref "U4") (pin "27") (pinfunction "AN12/RB12_27") (pintype "passive"))
    )
    (net (code "52") (name "/LightN_OUT") (class "Default")
      (node (ref "D5") (pin "1") (pinfunction "A_1") (pintype "passive"))
      (node (ref "J5") (pin "7") (pinfunction "7_7") (pintype "passive"))
      (node (ref "Q3") (pin "1") (pinfunction "D_1") (pintype "passive"))
    )
    (net (code "53") (name "/LightR") (class "Default")
      (node (ref "Q5") (pin "3") (pinfunction "G_3") (pintype "passive"))
      (node (ref "R35") (pin "1") (pinfunction "1_1") (pintype "passive"))
      (node (ref "U4") (pin "28") (pinfunction "AN13/RB13_28") (pintype "passive"))
    )
    (net (code "54") (name "/LightR_OUT") (class "Default")
      (node (ref "D8") (pin "1") (pinfunction "A_1") (pintype "passive"))
      (node (ref "J5") (pin "8") (pinfunction "8_8") (pintype "passive"))
      (node (ref "Q5") (pin "1") (pinfunction "D_1") (pintype "passive"))
    )
    (net (code "55") (name "/MCLR") (class "Default")
      (node (ref "J3") (pin "1") (pinfunction "1_1") (pintype "passive"))
      (node (ref "R44") (pin "1") (pinfunction "1_1") (pintype "passive"))
      (node (ref "U4") (pin "7") (pinfunction "~{MCLR}_7") (pintype "passive"))
    )
    (net (code "56") (name "/PGC") (class "Default")
      (node (ref "J3") (pin "5") (pinfunction "5_5") (pintype "passive"))
      (node (ref "U4") (pin "17") (pinfunction "PGC/EMUC/AN6/OCFA/RB6_17") (pintype "passive"))
    )
    (net (code "57") (name "/PGD") (class "Default")
      (node (ref "J3") (pin "4") (pinfunction "4_4") (pintype "passive"))
      (node (ref "U4") (pin "18") (pinfunction "PGD/EMUD/AN7/RB7_18") (pintype "passive"))
    )
    (net (code "58") (name "/RESET") (class "Default")
      (node (ref "C23") (pin "2") (pinfunction "2_2") (pintype "passive"))
      (node (ref "D13") (pin "1") (pinfunction "A_1") (pintype "passive"))
      (node (ref "R42") (pin "2") (pinfunction "2_2") (pintype "passive"))
      (node (ref "R44") (pin "2") (pinfunction "2_2") (pintype "passive"))
      (node (ref "U5") (pin "1") (pinfunction "~{RST}_1") (pintype "passive"))
    )
    (net (code "59") (name "/RX") (class "Default")
      (node (ref "J2") (pin "10") (pinfunction "10_10") (pintype "passive"))
      (node (ref "U4") (pin "34") (pinfunction "U1RX/SDI1/RF2_34") (pintype "passive"))
    )
    (net (code "60") (name "/TX") (class "Default")
      (node (ref "J2") (pin "8") (pinfunction "8_8") (pintype "passive"))
      (node (ref "U4") (pin "33") (pinfunction "EMUD3/U1TX/SDO1/RF3_33") (pintype "passive"))
    )
    (net (code "61") (name "/WDI") (class "Default")
      (node (ref "R33") (pin "1") (pinfunction "1_1") (pintype "passive"))
      (node (ref "U5") (pin "4") (pinfunction "WDI_4") (pintype "passive"))
    )
    (net (code "62") (name "GND") (class "Default")
      (node (ref "C1") (pin "2") (pinfunction "2_2") (pintype "passive"))
      (node (ref "C10") (pin "2") (pinfunction "2_2") (pintype "passive"))
      (node (ref "C11") (pin "2") (pinfunction "2_2") (pintype "passive"))
      (node (ref "C12") (pin "2") (pinfunction "2_2") (pintype "passive"))
      (node (ref "C13") (pin "2") (pinfunction "2_2") (pintype "passive"))
      (node (ref "C14") (pin "2") (pinfunction "2_2") (pintype "passive"))
      (node (ref "C15") (pin "2") (pinfunction "2_2") (pintype "passive"))
      (node (ref "C16") (pin "2") (pinfunction "2_2") (pintype "passive"))
      (node (ref "C17") (pin "2") (pinfunction "2_2") (pintype "passive"))
      (node (ref "C18") (pin "2") (pinfunction "2_2") (pintype "passive"))
      (node (ref "C19") (pin "2") (pinfunction "2_2") (pintype "passive"))
      (node (ref "C2") (pin "1") (pinfunction "1_1") (pintype "passive"))
      (node (ref "C20") (pin "2") (pinfunction "2_2") (pintype "passive"))
      (node (ref "C21") (pin "2") (pinfunction "2_2") (pintype "passive"))
      (node (ref "C22") (pin "2") (pinfunction "2_2") (pintype "passive"))
      (node (ref "C23") (pin "1") (pinfunction "1_1") (pintype "passive"))
      (node (ref "C24") (pin "1") (pinfunction "1_1") (pintype "passive"))
      (node (ref "C3") (pin "2") (pinfunction "2_2") (pintype "passive"))
      (node (ref "C4") (pin "2") (pinfunction "2_2") (pintype "passive"))
      (node (ref "C5") (pin "2") (pinfunction "2_2") (pintype "passive"))
      (node (ref "C6") (pin "2") (pinfunction "2_2") (pintype "passive"))
      (node (ref "C7") (pin "1") (pinfunction "1_1") (pintype "passive"))
      (node (ref "C8") (pin "2") (pinfunction "2_2") (pintype "passive"))
      (node (ref "C9") (pin "1") (pinfunction "1_1") (pintype "passive"))
      (node (ref "D10") (pin "1") (pinfunction "A_1") (pintype "passive"))
      (node (ref "D11") (pin "1") (pinfunction "A_1") (pintype "passive"))
      (node (ref "D12") (pin "1") (pinfunction "A_1") (pintype "passive"))
      (node (ref "D2") (pin "1") (pinfunction "A_1") (pintype "passive"))
      (node (ref "D4") (pin "1") (pinfunction "A_1") (pintype "passive"))
      (node (ref "D6") (pin "1") (pinfunction "A_1") (pintype "passive"))
      (node (ref "D7") (pin "1") (pinfunction "A_1") (pintype "passive"))
      (node (ref "D9") (pin "1") (pinfunction "A_1") (pintype "passive"))
      (node (ref "J1") (pin "14") (pinfunction "14_14") (pintype "passive"))
      (node (ref "J2") (pin "12") (pinfunction "12_12") (pintype "passive"))
      (node (ref "J2") (pin "14") (pinfunction "14_14") (pintype "passive"))
      (node (ref "J3") (pin "3") (pinfunction "3_3") (pintype "passive"))
      (node (ref "J4") (pin "1") (pinfunction "1_1") (pintype "passive"))
      (node (ref "J5") (pin "1") (pinfunction "1_1") (pintype "passive"))
      (node (ref "LED4") (pin "2") (pinfunction "K_2") (pintype "passive"))
      (node (ref "Q1") (pin "2") (pinfunction "S_2") (pintype "passive"))
      (node (ref "Q2") (pin "2") (pinfunction "S_2") (pintype "passive"))
      (node (ref "Q3") (pin "2") (pinfunction "S_2") (pintype "passive"))
      (node (ref "Q4") (pin "2") (pinfunction "S_2") (pintype "passive"))
      (node (ref "Q5") (pin "2") (pinfunction "S_2") (pintype "passive"))
      (node (ref "Q6") (pin "2") (pinfunction "S_2") (pintype "passive"))
      (node (ref "Q7") (pin "2") (pinfunction "S_2") (pintype "passive"))
      (node (ref "R1") (pin "1") (pinfunction "1_1") (pintype "passive"))
      (node (ref "R11") (pin "1") (pinfunction "1_1") (pintype "passive"))
      (node (ref "R13") (pin "1") (pinfunction "1_1") (pintype "passive"))
      (node (ref "R14") (pin "2") (pinfunction "2_2") (pintype "passive"))
      (node (ref "R15") (pin "2") (pinfunction "2_2") (pintype "passive"))
      (node (ref "R18") (pin "2") (pinfunction "2_2") (pintype "passive"))
      (node (ref "R2") (pin "2") (pinfunction "2_2") (pintype "passive"))
      (node (ref "R24") (pin "2") (pinfunction "2_2") (pintype "passive"))
      (node (ref "R28") (pin "2") (pinfunction "2_2") (pintype "passive"))
      (node (ref "R34") (pin "2") (pinfunction "2_2") (pintype "passive"))
      (node (ref "R35") (pin "2") (pinfunction "2_2") (pintype "passive"))
      (node (ref "R45") (pin "2") (pinfunction "2_2") (pintype "passive"))
      (node (ref "R46") (pin "2") (pinfunction "2_2") (pintype "passive"))
      (node (ref "R6") (pin "2") (pinfunction "2_2") (pintype "passive"))
      (node (ref "S1") (pin "1") (pintype "passive"))
      (node (ref "U1") (pin "2") (pinfunction "GND_2") (pintype "power_in"))
      (node (ref "U2") (pin "4") (pinfunction "GND_4") (pintype "power_in"))
      (node (ref "U3") (pin "2") (pinfunction "GND_2") (pintype "power_in"))
      (node (ref "U4") (pin "20") (pinfunction "AVSS_20") (pintype "passive"))
      (node (ref "U4") (pin "25") (pinfunction "VSS_25") (pintype "passive"))
      (node (ref "U4") (pin "41") (pinfunction "VSS_41") (pintype "passive"))
      (node (ref "U4") (pin "56") (pinfunction "VSS_56") (pintype "passive"))
      (node (ref "U4") (pin "9") (pinfunction "VSS_9") (pintype "passive"))
      (node (ref "U5") (pin "2") (pinfunction "Vss_2") (pintype "passive"))
    )
    (net (code "63") (name "Net-(C2-Pad2)") (class "Default")
      (node (ref "C2") (pin "2") (pinfunction "2_2") (pintype "passive"))
      (node (ref "R3") (pin "2") (pinfunction "2_2") (pintype "passive"))
      (node (ref "R8") (pin "2") (pinfunction "2_2") (pintype "passive"))
      (node (ref "R9") (pin "2") (pinfunction "2_2") (pintype "passive"))
    )
    (net (code "64") (name "Net-(C9-Pad2)") (class "Default")
      (node (ref "C9") (pin "2") (pinfunction "2_2") (pintype "passive"))
      (node (ref "R16") (pin "2") (pinfunction "2_2") (pintype "passive"))
      (node (ref "R19") (pin "2") (pinfunction "2_2") (pintype "passive"))
      (node (ref "R20") (pin "2") (pinfunction "2_2") (pintype "passive"))
    )
    (net (code "65") (name "Net-(D2-K)") (class "Default")
      (node (ref "D2") (pin "2") (pinfunction "K_2") (pintype "passive"))
      (node (ref "L1") (pin "1") (pinfunction "1_1") (pintype "passive"))
      (node (ref "U2") (pin "2") (pinfunction "SWE_2") (pintype "open_emitter"))
    )
    (net (code "66") (name "Net-(D3-K)") (class "Default")
      (node (ref "D3") (pin "2") (pinfunction "K_2") (pintype "passive"))
      (node (ref "R21") (pin "2") (pinfunction "2_2") (pintype "passive"))
    )
    (net (code "67") (name "Net-(D5-K)") (class "Default")
      (node (ref "D5") (pin "2") (pinfunction "K_2") (pintype "passive"))
      (node (ref "R25") (pin "2") (pinfunction "2_2") (pintype "passive"))
    )
    (net (code "68") (name "Net-(D8-K)") (class "Default")
      (node (ref "D8") (pin "2") (pinfunction "K_2") (pintype "passive"))
      (node (ref "R29") (pin "2") (pinfunction "2_2") (pintype "passive"))
    )
    (net (code "69") (name "Net-(D14-A)") (class "Default")
      (node (ref "C24") (pin "2") (pinfunction "2_2") (pintype "passive"))
      (node (ref "D14") (pin "1") (pinfunction "A_1") (pintype "passive"))
      (node (ref "R43") (pin "1") (pinfunction "1_1") (pintype "passive"))
      (node (ref "S1") (pin "2") (pintype "passive"))
      (node (ref "U5") (pin "3") (pinfunction "~{MR}_3") (pintype "passive"))
    )
    (net (code "70") (name "Net-(LED1-K)") (class "Default")
      (node (ref "LED1") (pin "2") (pinfunction "K_2") (pintype "passive"))
      (node (ref "R5") (pin "1") (pinfunction "1_1") (pintype "passive"))
    )
    (net (code "71") (name "Net-(LED2-K)") (class "Default")
      (node (ref "LED2") (pin "2") (pinfunction "K_2") (pintype "passive"))
      (node (ref "R15") (pin "1") (pinfunction "1_1") (pintype "passive"))
    )
    (net (code "72") (name "Net-(LED3-K)") (class "Default")
      (node (ref "LED3") (pin "2") (pinfunction "K_2") (pintype "passive"))
      (node (ref "R17") (pin "1") (pinfunction "1_1") (pintype "passive"))
    )
    (net (code "73") (name "Net-(LED4-A)") (class "Default")
      (node (ref "LED4") (pin "1") (pinfunction "A_1") (pintype "passive"))
      (node (ref "R12") (pin "2") (pinfunction "2_2") (pintype "passive"))
    )
    (net (code "74") (name "Net-(LED5-K)") (class "Default")
      (node (ref "LED5") (pin "2") (pinfunction "K_2") (pintype "passive"))
      (node (ref "R30") (pin "1") (pinfunction "1_1") (pintype "passive"))
    )
    (net (code "75") (name "Net-(Q1-G)") (class "Default")
      (node (ref "Q1") (pin "3") (pinfunction "G_3") (pintype "passive"))
      (node (ref "R10") (pin "2") (pinfunction "2_2") (pintype "passive"))
    )
    (net (code "76") (name "Net-(Q4-D)") (class "Default")
      (node (ref "Q4") (pin "1") (pinfunction "D_1") (pintype "passive"))
      (node (ref "R21") (pin "1") (pinfunction "1_1") (pintype "passive"))
      (node (ref "R25") (pin "1") (pinfunction "1_1") (pintype "passive"))
      (node (ref "R29") (pin "1") (pinfunction "1_1") (pintype "passive"))
    )
    (net (code "77") (name "Net-(U1-RS)") (class "Default")
      (node (ref "R6") (pin "1") (pinfunction "1_1") (pintype "passive"))
      (node (ref "U1") (pin "8") (pinfunction "RS_8") (pintype "passive"))
    )
    (net (code "78") (name "Net-(U1-VREF)") (class "Default")
      (node (ref "R3") (pin "1") (pinfunction "1_1") (pintype "passive"))
      (node (ref "U1") (pin "5") (pinfunction "VREF_5") (pintype "output"))
    )
    (net (code "79") (name "Net-(U2--VIN)") (class "Default")
      (node (ref "R11") (pin "2") (pinfunction "2_2") (pintype "passive"))
      (node (ref "R7") (pin "2") (pinfunction "2_2") (pintype "passive"))
      (node (ref "U2") (pin "5") (pinfunction "-VIN_5") (pintype "input"))
    )
    (net (code "80") (name "Net-(U2-DRVC)") (class "Default")
      (node (ref "R4") (pin "1") (pinfunction "1_1") (pintype "passive"))
      (node (ref "U2") (pin "1") (pinfunction "SWC_1") (pintype "open_collector"))
      (node (ref "U2") (pin "7") (pinfunction "IPK_7") (pintype "passive"))
      (node (ref "U2") (pin "8") (pinfunction "DRVC_8") (pintype "open_collector"))
    )
    (net (code "81") (name "Net-(U2-TCAP)") (class "Default")
      (node (ref "C7") (pin "2") (pinfunction "2_2") (pintype "passive"))
      (node (ref "U2") (pin "3") (pinfunction "TCAP_3") (pintype "passive"))
    )
    (net (code "82") (name "Net-(U3-RS)") (class "Default")
      (node (ref "R18") (pin "1") (pinfunction "1_1") (pintype "passive"))
      (node (ref "U3") (pin "8") (pinfunction "RS_8") (pintype "passive"))
    )
    (net (code "83") (name "Net-(U3-VREF)") (class "Default")
      (node (ref "R16") (pin "1") (pinfunction "1_1") (pintype "passive"))
      (node (ref "U3") (pin "5") (pinfunction "VREF_5") (pintype "output"))
    )
    (net (code "84") (name "Net-(U4-OSC1{slash}CLKI)") (class "Default")
      (node (ref "C17") (pin "1") (pinfunction "1_1") (pintype "passive"))
      (node (ref "U4") (pin "39") (pinfunction "OSC1/CLKI_39") (pintype "passive"))
      (node (ref "Y1") (pin "2") (pinfunction "OSC2_2") (pintype "passive"))
    )
    (net (code "85") (name "Net-(U4-OSC2{slash}CLKO{slash}RC15)") (class "Default")
      (node (ref "C18") (pin "1") (pinfunction "1_1") (pintype "passive"))
      (node (ref "U4") (pin "40") (pinfunction "OSC2/CLKO/RC15_40") (pintype "passive"))
      (node (ref "Y1") (pin "1") (pinfunction "OSC1_1") (pintype "passive"))
    )
    (net (code "86") (name "Net-(U4-SCL{slash}RG2)") (class "Default")
      (node (ref "R30") (pin "2") (pinfunction "2_2") (pintype "passive"))
      (node (ref "U4") (pin "37") (pinfunction "SCL/RG2_37") (pintype "passive"))
    )
    (net (code "87") (name "Net-(U4-~{SS2}{slash}CN11{slash}RG9)") (class "Default")
      (node (ref "R33") (pin "2") (pinfunction "2_2") (pintype "passive"))
      (node (ref "U4") (pin "8") (pinfunction "~{SS2}/CN11/RG9_8") (pintype "passive"))
    )
    (net (code "88") (name "unconnected-(U4-COFS{slash}RG15-Pad1)") (class "Default")
      (node (ref "U4") (pin "1") (pinfunction "COFS/RG15_1") (pintype "passive"))
    )
    (net (code "89") (name "unconnected-(U4-CSCK{slash}RG14-Pad62)") (class "Default")
      (node (ref "U4") (pin "62") (pinfunction "CSCK/RG14_62") (pintype "passive"))
    )
    (net (code "90") (name "unconnected-(U4-CSDI{slash}RG12-Pad63)") (class "Default")
      (node (ref "U4") (pin "63") (pinfunction "CSDI/RG12_63") (pintype "passive"))
    )
    (net (code "91") (name "unconnected-(U4-CSDO{slash}RG13-Pad64)") (class "Default")
      (node (ref "U4") (pin "64") (pinfunction "CSDO/RG13_64") (pintype "passive"))
    )
    (net (code "92") (name "unconnected-(U4-EMUC3{slash}SCK1{slash}INT0{slash}RF6-Pad35)") (class "Default")
      (node (ref "U4") (pin "35") (pinfunction "EMUC3/SCK1/INT0/RF6_35") (pintype "passive"))
    )
    (net (code "93") (name "unconnected-(U4-SCK2{slash}CN8{slash}RG6-Pad4)") (class "Default")
      (node (ref "U4") (pin "4") (pinfunction "SCK2/CN8/RG6_4") (pintype "passive"))
    )
    (net (code "94") (name "unconnected-(U4-SDA{slash}RG3-Pad36)") (class "Default")
      (node (ref "U4") (pin "36") (pinfunction "SDA/RG3_36") (pintype "passive"))
    )
    (net (code "95") (name "unconnected-(U4-SDI2{slash}CN9{slash}RG7-Pad5)") (class "Default")
      (node (ref "U4") (pin "5") (pinfunction "SDI2/CN9/RG7_5") (pintype "passive"))
    )
    (net (code "96") (name "unconnected-(U4-SDO2{slash}CN10{slash}RG8-Pad6)") (class "Default")
      (node (ref "U4") (pin "6") (pinfunction "SDO2/CN10/RG8_6") (pintype "passive"))
    )
    (net (code "97") (name "unconnected-(U4-T2CK{slash}RC1-Pad2)") (class "Default")
      (node (ref "U4") (pin "2") (pinfunction "T2CK/RC1_2") (pintype "passive"))
    )
    (net (code "98") (name "unconnected-(U4-T3CK{slash}RC2-Pad3)") (class "Default")
      (node (ref "U4") (pin "3") (pinfunction "T3CK/RC2_3") (pintype "passive"))
    )
  )
)
